# Sheet1.net
KiCad netlist of a schematic drawn in Altium Designer
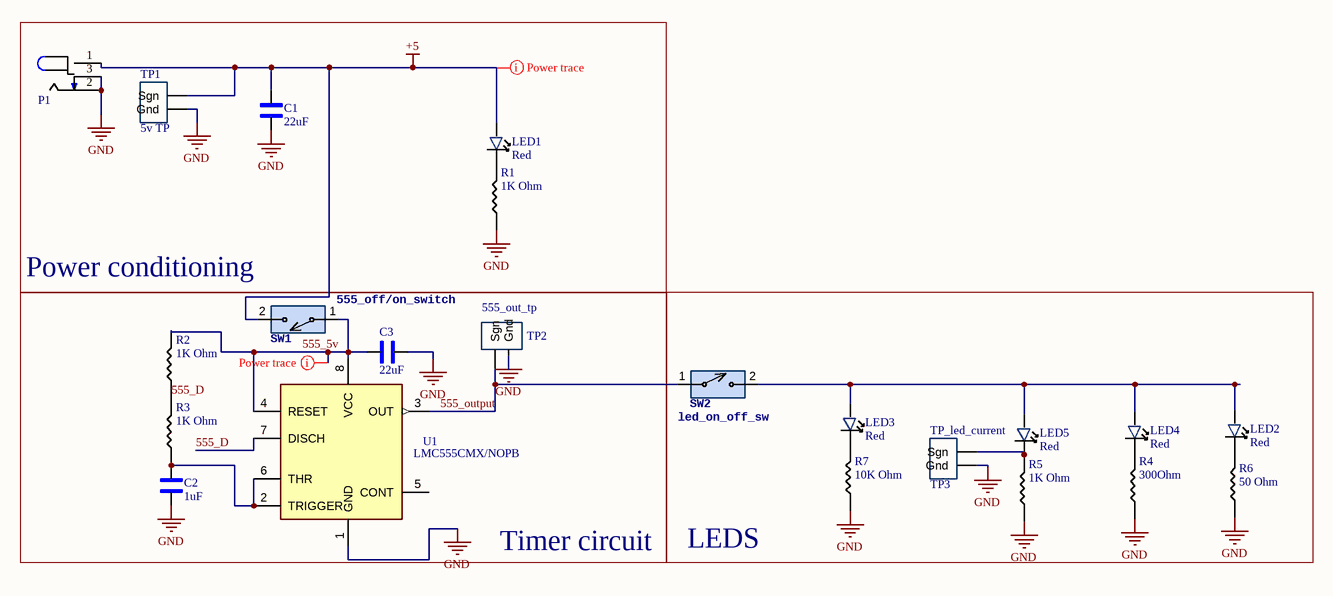
[diagram p0: Sheet1.SchDoc]

(export (version "E")
  (design (tool "Eeschema 10.0.6"))
  (components
    (comp (ref "C1")
      (value "22uF")
      (footprint "1206_Passive_Capacitor")
      (description "22uF ±10% 25V X5R 1206 Multilayer Ceramic Capacitors MLCC - SMD/SMT RoHS")
      (fields (field (name "MFR PART #") "CL31A226KAHNNNE") (field (name "LCSC PART#") "C12891"))
      (libsource (lib "ECEN5730Lib_2023_05_DS") (part "C_22uF_1206"))
    )
    (comp (ref "C2")
      (value "1uF")
      (footprint "1206_Passive_Capacitor")
      (description "MULTILAYER CERAMIC CAPACITORS MLCC - SMD/SMT 1UF 50V 1206 ROHS")
      (fields (field (name "MFR PART #") "CL31B105KBHNNNE") (field (name "LCSC PART#") "C1848"))
      (libsource (lib "ECEN5730Lib_2023_05_DS") (part "C_1uF_1206"))
    )
    (comp (ref "C3")
      (value "22uF")
      (footprint "1206_Passive_Capacitor")
      (description "22uF ±10% 25V X5R 1206 Multilayer Ceramic Capacitors MLCC - SMD/SMT RoHS")
      (fields (field (name "MFR PART #") "CL31A226KAHNNNE") (field (name "LCSC PART#") "C12891"))
      (libsource (lib "ECEN5730Lib_2023_05_DS") (part "C_22uF_1206"))
    )
    (comp (ref "LED1")
      (value "Red")
      (footprint "LED_1206")
      (description "Red 621~631nm 1206 Light Emitting Diodes (LED) RoHS")
      (fields (field (name "MFR PART #") "15-21/R6C-FQ1R1B/2T") (field (name "LCSC PART#") "C93133"))
      (libsource (lib "ECEN5730Lib_2023_05_DS") (part "LED_RED_1206"))
    )
    (comp (ref "LED2")
      (value "Red")
      (footprint "LED_1206")
      (description "Red 621~631nm 1206 Light Emitting Diodes (LED) RoHS")
      (fields (field (name "MFR PART #") "15-21/R6C-FQ1R1B/2T") (field (name "LCSC PART#") "C93133"))
      (libsource (lib "ECEN5730Lib_2023_05_DS") (part "LED_RED_1206"))
    )
    (comp (ref "LED3")
      (value "Red")
      (footprint "LED_1206")
      (description "Red 621~631nm 1206 Light Emitting Diodes (LED) RoHS")
      (fields (field (name "MFR PART #") "15-21/R6C-FQ1R1B/2T") (field (name "LCSC PART#") "C93133"))
      (libsource (lib "ECEN5730Lib_2023_05_DS") (part "LED_RED_1206"))
    )
    (comp (ref "LED4")
      (value "Red")
      (footprint "LED_1206")
      (description "Red 621~631nm 1206 Light Emitting Diodes (LED) RoHS")
      (fields (field (name "MFR PART #") "15-21/R6C-FQ1R1B/2T") (field (name "LCSC PART#") "C93133"))
      (libsource (lib "ECEN5730Lib_2023_05_DS") (part "LED_RED_1206"))
    )
    (comp (ref "LED5")
      (value "Red")
      (footprint "LED_1206")
      (description "Red 621~631nm 1206 Light Emitting Diodes (LED) RoHS")
      (fields (field (name "MFR PART #") "15-21/R6C-FQ1R1B/2T") (field (name "LCSC PART#") "C93133"))
      (libsource (lib "ECEN5730Lib_2023_05_DS") (part "LED_RED_1206"))
    )
    (comp (ref "P1")
      (value "Power Jack")
      (footprint "Power_Jack")
      (description "Power Barrel Connector Jack 2.10mm ID (0.083\"), 5.50mm OD (0.217\") Through Hole, Right Angle")
      (fields (field (name "MFR PART #") "PJ-102A") (field (name "LCSC PART#") "C136744"))
      (libsource (lib "ECEN5730Lib_2023_05_DS") (part "P_Power Jack"))
    )
    (comp (ref "R1")
      (value "1K Ohm")
      (footprint "1206_Passive_Resitor")
      (description "CHIP RESISTOR - SURFACE MOUNT 1KOHMS ±1% 1/4W 1206 ROHS")
      (fields (field (name "MFR PART #") "RNCP1206FTD1K00CT") (field (name "LCSC PART#") "C4410"))
      (libsource (lib "ECEN5730Lib_2023_05_DS") (part "R_1K_1206"))
    )
    (comp (ref "R2")
      (value "1K Ohm")
      (footprint "1206_Passive_Resitor")
      (description "CHIP RESISTOR - SURFACE MOUNT 1KOHMS ±1% 1/4W 1206 ROHS")
      (fields (field (name "MFR PART #") "RNCP1206FTD1K00CT") (field (name "LCSC PART#") "C4410"))
      (libsource (lib "ECEN5730Lib_2023_05_DS") (part "R_1K_1206"))
    )
    (comp (ref "R3")
      (value "1K Ohm")
      (footprint "1206_Passive_Resitor")
      (description "CHIP RESISTOR - SURFACE MOUNT 1KOHMS ±1% 1/4W 1206 ROHS")
      (fields (field (name "MFR PART #") "RNCP1206FTD1K00CT") (field (name "LCSC PART#") "C4410"))
      (libsource (lib "ECEN5730Lib_2023_05_DS") (part "R_1K_1206"))
    )
    (comp (ref "R4")
      (value "300Ohm")
      (footprint "1206_Passive_Resitor")
      (description "CHIP RESISTOR - SURFACE MOUNT 300OHMS ±1% 1/4W 1206 ROHS")
      (fields (field (name "MFR PART #") "1206W4F3000T5E") (field (name "LCSC PART#") "C17887"))
      (libsource (lib "ECEN5730Lib_2023_05_DS") (part "R_300Ohm_1206"))
    )
    (comp (ref "R5")
      (value "1K Ohm")
      (footprint "1206_Passive_Resitor")
      (description "CHIP RESISTOR - SURFACE MOUNT 1KOHMS ±1% 1/4W 1206 ROHS")
      (fields (field (name "MFR PART #") "RNCP1206FTD1K00CT") (field (name "LCSC PART#") "C4410"))
      (libsource (lib "ECEN5730Lib_2023_05_DS") (part "R_1K_1206"))
    )
    (comp (ref "R6")
      (value "50 Ohm")
      (footprint "1206_Passive_Resitor")
      (description "CHIP RESISTOR - SURFACE MOUNT 100MOHMS ±1% 1/4W 1206 ROHS")
      (fields (field (name "MFR PART #") "1206W4F1006T5E") (field (name "LCSC PART#") "C59781"))
      (libsource (lib "ECEN5730Lib_2023_05_DS") (part "R_100M_1206_1"))
    )
    (comp (ref "R7")
      (value "10K Ohm")
      (footprint "1206_Passive_Resitor")
      (description "CHIP RESISTOR - SURFACE MOUNT 100MOHMS ±1% 1/4W 1206 ROHS")
      (fields (field (name "MFR PART #") "1206W4F1006T5E") (field (name "LCSC PART#") "C59781"))
      (libsource (lib "ECEN5730Lib_2023_05_DS") (part "R_100M_1206_1"))
    )
    (comp (ref "SW1")
      (value "555_off/on_switch")
      (footprint "2Pin-Header-Conn")
      (description "2Pin Header")
      (fields (field (name "LCSC PART#") "C124375"))
      (libsource (lib "ECEN5730Lib_2023_05_DS") (part "SW_2Pin_100mil_Switch"))
    )
    (comp (ref "SW2")
      (value "led_on_off_sw")
      (footprint "2Pin-Header-Conn")
      (description "2Pin Header")
      (fields (field (name "LCSC PART#") "C124375"))
      (libsource (lib "") (part "SW_2Pin_100mil_Switch_1"))
    )
    (comp (ref "TP1")
      (value "5v TP")
      (footprint "TP10x_Probe")
      (description "Test Point 300 mil centers")
      (libsource (lib "") (part "TP_10x_Probe_1"))
    )
    (comp (ref "TP2")
      (value "555_out_tp")
      (footprint "TP10x_Probe")
      (description "Test Point 300 mil centers")
      (libsource (lib "ECEN5730Lib_2023_05_DS") (part "TP_10x_Probe"))
    )
    (comp (ref "TP3")
      (value "TP_led_current")
      (footprint "TP10x_Probe")
      (description "Test Point 300 mil centers")
      (libsource (lib "") (part "TP_10x_Probe_1"))
    )
    (comp (ref "U1")
      (value "LMC555CMX/NOPB")
      (footprint "TS555IDTTR")
      (description "555 Type, Timer/Oscillator _Single_ IC 3MHz 8-SO")
      (fields (field (name "LCSC PART#") "C90760"))
      (libsource (lib "ECEN5730Lib_2023_05_DS") (part "U_555_Fast"))
    )
  )
  (nets
    (net (code "1") (name "+5") (class "Default")
      (node (ref "C1") (pin "2") (pinfunction "2_2") (pintype "passive"))
      (node (ref "LED1") (pin "1") (pinfunction "1_1") (pintype "passive"))
      (node (ref "P1") (pin "1") (pinfunction "1_1") (pintype "power_in"))
      (node (ref "SW1") (pin "2") (pinfunction "2_2") (pintype "passive"))
      (node (ref "TP1") (pin "1") (pinfunction "Sgn_1") (pintype "passive"))
    )
    (net (code "2") (name "/555_5v") (class "Default")
      (node (ref "C3") (pin "1") (pinfunction "1_1") (pintype "passive"))
      (node (ref "R2") (pin "2") (pinfunction "2_2") (pintype "passive"))
      (node (ref "SW1") (pin "1") (pinfunction "1_1") (pintype "passive"))
      (node (ref "U1") (pin "4") (pinfunction "RESET_4") (pintype "passive"))
      (node (ref "U1") (pin "8") (pinfunction "VCC_8") (pintype "power_in"))
    )
    (net (code "3") (name "/555_D") (class "Default")
      (node (ref "R2") (pin "1") (pinfunction "1_1") (pintype "passive"))
      (node (ref "R3") (pin "2") (pinfunction "2_2") (pintype "passive"))
      (node (ref "U1") (pin "7") (pinfunction "DISCH_7") (pintype "passive"))
    )
    (net (code "4") (name "/555_output") (class "Default")
      (node (ref "SW2") (pin "1") (pinfunction "1_1") (pintype "passive"))
      (node (ref "TP2") (pin "1") (pinfunction "Sgn_1") (pintype "passive"))
      (node (ref "U1") (pin "3") (pinfunction "OUT_3") (pintype "output"))
    )
    (net (code "5") (name "GND") (class "Default")
      (node (ref "C1") (pin "1") (pinfunction "1_1") (pintype "passive"))
      (node (ref "C2") (pin "1") (pinfunction "1_1") (pintype "passive"))
      (node (ref "C3") (pin "2") (pinfunction "2_2") (pintype "passive"))
      (node (ref "P1") (pin "2") (pinfunction "2_2") (pintype "power_in"))
      (node (ref "P1") (pin "3") (pinfunction "3_3") (pintype "power_in"))
      (node (ref "R1") (pin "1") (pinfunction "1_1") (pintype "passive"))
      (node (ref "R4") (pin "1") (pinfunction "1_1") (pintype "passive"))
      (node (ref "R5") (pin "1") (pinfunction "1_1") (pintype "passive"))
      (node (ref "R6") (pin "1") (pinfunction "1_1") (pintype "passive"))
      (node (ref "R7") (pin "1") (pinfunction "1_1") (pintype "passive"))
      (node (ref "TP1") (pin "2") (pinfunction "Gnd_2") (pintype "passive"))
      (node (ref "TP2") (pin "2") (pinfunction "Gnd_2") (pintype "passive"))
      (node (ref "TP3") (pin "2") (pinfunction "Gnd_2") (pintype "passive"))
      (node (ref "U1") (pin "1") (pinfunction "GND_1") (pintype "power_in"))
    )
    (net (code "6") (name "Net-(LED1-Pad2)") (class "Default")
      (node (ref "LED1") (pin "2") (pinfunction "2_2") (pintype "passive"))
      (node (ref "R1") (pin "2") (pinfunction "2_2") (pintype "passive"))
    )
    (net (code "7") (name "Net-(LED2-Pad1)") (class "Default")
      (node (ref "LED2") (pin "1") (pinfunction "1_1") (pintype "passive"))
      (node (ref "LED3") (pin "1") (pinfunction "1_1") (pintype "passive"))
      (node (ref "LED4") (pin "1") (pinfunction "1_1") (pintype "passive"))
      (node (ref "LED5") (pin "1") (pinfunction "1_1") (pintype "passive"))
      (node (ref "SW2") (pin "2") (pinfunction "2_2") (pintype "passive"))
    )
    (net (code "8") (name "Net-(LED2-Pad2)") (class "Default")
      (node (ref "LED2") (pin "2") (pinfunction "2_2") (pintype "passive"))
      (node (ref "R6") (pin "2") (pinfunction "2_2") (pintype "passive"))
    )
    (net (code "9") (name "Net-(LED3-Pad2)") (class "Default")
      (node (ref "LED3") (pin "2") (pinfunction "2_2") (pintype "passive"))
      (node (ref "R7") (pin "2") (pinfunction "2_2") (pintype "passive"))
    )
    (net (code "10") (name "Net-(LED4-Pad2)") (class "Default")
      (node (ref "LED4") (pin "2") (pinfunction "2_2") (pintype "passive"))
      (node (ref "R4") (pin "2") (pinfunction "2_2") (pintype "passive"))
    )
    (net (code "11") (name "Net-(TP3-Sgn)") (class "Default")
      (node (ref "LED5") (pin "2") (pinfunction "2_2") (pintype "passive"))
      (node (ref "R5") (pin "2") (pinfunction "2_2") (pintype "passive"))
      (node (ref "TP3") (pin "1") (pinfunction "Sgn_1") (pintype "passive"))
    )
    (net (code "12") (name "Net-(U1-THR)") (class "Default")
      (node (ref "C2") (pin "2") (pinfunction "2_2") (pintype "passive"))
      (node (ref "R3") (pin "1") (pinfunction "1_1") (pintype "passive"))
      (node (ref "U1") (pin "2") (pinfunction "TRIGGER_2") (pintype "passive"))
      (node (ref "U1") (pin "6") (pinfunction "THR_6") (pintype "passive"))
    )
    (net (code "13") (name "unconnected-(U1-CONT-Pad5)") (class "Default")
      (node (ref "U1") (pin "5") (pinfunction "CONT_5") (pintype "passive"))
    )
  )
)
